# 04-POWER-P12V.net
KiCad netlist of a schematic drawn in Altium Designer
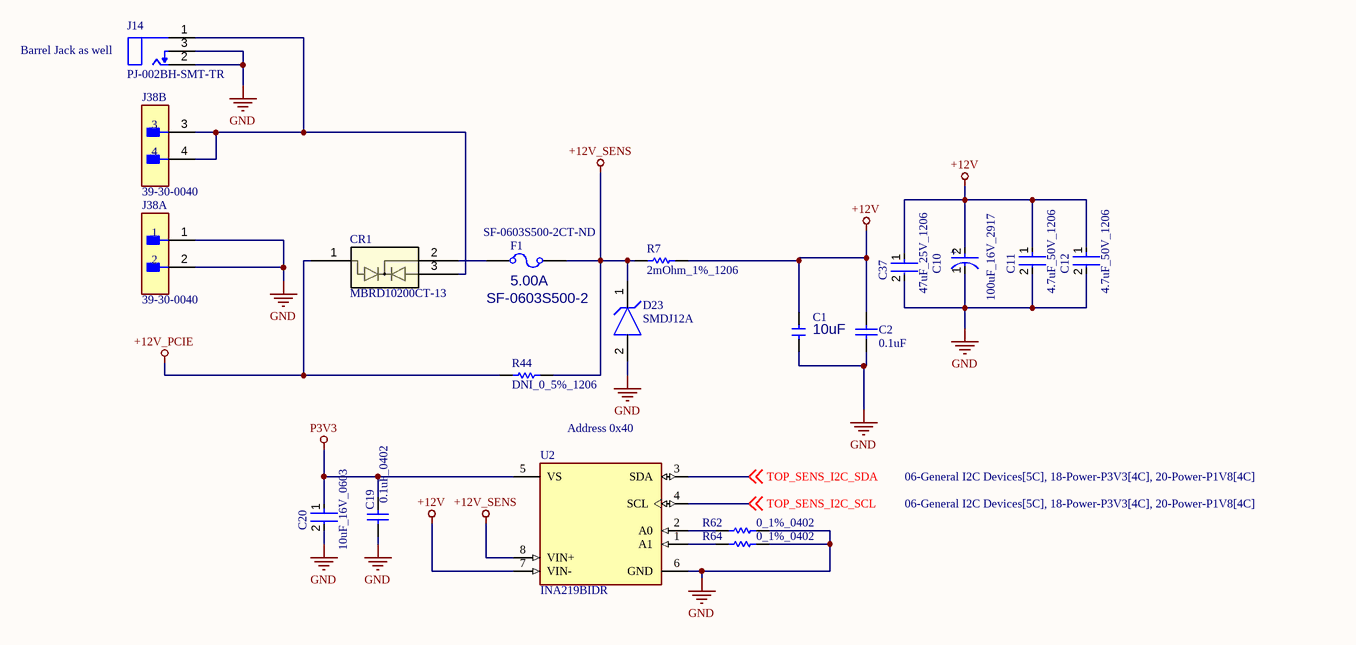
[diagram p0: 04-POWER-P12V.SchDoc]

(export (version "E")
  (design (tool "Eeschema 10.0.6"))
  (components
    (comp (ref "C1")
      (value "10uF")
      (footprint "CAPC2012X14N")
      (description "CAP, CER, 10.UF, 25V, 10%, X5R, 0805")
      (fields
        (field (name "MFG PART NUM") "TMK212BBJ106KG-T")
        (field (name "VALENTIUM PART NUM") "<VALENTIUM>")
      )
      (libsource (lib "Capacitors") (part "CAP_0805_10UF_25V"))
    )
    (comp (ref "C2")
      (value "0.1uF")
      (footprint "CAPC1608X87X45ML20T05")
      (description "C0603X104K5RACAUTO")
      (fields (field (name "MANUFACTURER") "Kemet"))
      (libsource (lib "Altium Content Vault") (part "CAP"))
    )
    (comp (ref "C10")
      (value "100uF_16V_2917")
      (footprint "FP-T495D107K016ATE125-MFG")
      (description "CAP TANT 100UF 10% 16V 2917")
      (fields (field (name "VOLTAGE") "16V") (field (name "TOLERANCE") "10%"))
      (libsource (lib "Altium Content Vault") (part "a00bbbee19879c290e62620ae7e47b1"))
    )
    (comp (ref "C11")
      (value "4.7uF_50V_1206")
      (footprint "FP-GRM31C-0_2-e0_3_0_8-IPC_C")
      (description "Chip Multilayer Ceramic Capacitors for General Purpose, 1206, 4.7uF, X7R, 15%, 10%, 50V")
      (fields (field (name "VOLTAGE") "50V") (field (name "TOLERANCE") "10%"))
      (libsource (lib "Altium Content Vault") (part "02cd4be3c70576c341d710602a673aa"))
    )
    (comp (ref "C12")
      (value "4.7uF_50V_1206")
      (footprint "FP-GRM31C-0_2-e0_3_0_8-IPC_C")
      (description "Chip Multilayer Ceramic Capacitors for General Purpose, 1206, 4.7uF, X7R, 15%, 10%, 50V")
      (fields (field (name "VOLTAGE") "50V") (field (name "TOLERANCE") "10%"))
      (libsource (lib "Altium Content Vault") (part "02cd4be3c70576c341d710602a673aa"))
    )
    (comp (ref "C19")
      (value "0.1uF_0402")
      (footprint "CAPC1005X56X25NL10T15")
      (fields
        (field (name "PART NUMBER") "LD02YD104KAB2A")
        (field (name "MANUFACTURER") "AVX Interconnect / Elco")
      )
      (libsource (lib "Altium Content Vault") (part "CAP"))
    )
    (comp (ref "C20")
      (value "10uF_16V_0603")
      (footprint "FP-0603-L_1_6_0_2-W_0_8_0-MFG")
      (description "Multilayer Ceramic Capacitor 10uF 16V X5R 20% SMD 0603 T/R")
      (fields (field (name "TOLERANCE") "20%"))
      (libsource (lib "Altium Content Vault") (part "b4654b650e69147ec39a6b967a45e02"))
    )
    (comp (ref "C37")
      (value "47uF_25V_1206")
      (footprint "FP-C3216-160-0_2-MFG")
      (description "Multilayer Ceramic Capacitors 47uF ±20% 25V X5R SMD 1206")
      (fields (field (name "VOLTAGE") "25V") (field (name "TOLERANCE") "20%"))
      (libsource (lib "Altium Content Vault") (part "11868f565c42a9108669ba33697ecf6"))
    )
    (comp (ref "CR1")
      (value "MBRD10200CT-13")
      (footprint "TO252(DPAK)_DIO")
      (description "No Description Available")
      (libsource (lib "MBRD10200CT-13") (part "MBRD10200CT-13"))
    )
    (comp (ref "D23")
      (value "SMDJ12A")
      (footprint "FP-DO-214AB_SMC_J-Bend-MFG")
      (description "TVS DIODE 12V 19.9V DO214AB")
      (libsource (lib "Altium Content Vault") (part "673ecd2ea4d7fb87b4005b0cb348b7d"))
    )
    (comp (ref "F1")
      (value "5.00A")
      (footprint "FUSM1608X60N")
      (description "FUSE SLOW 5.00A 32V M 0603")
      (fields
        (field (name "MFG PART NUM") "SF-0603S500-2")
        (field (name "VALENTIUM PART NUM") "<VALENTIUM>")
        (field (name "SUPPLIER PART NUMBER 1") "SF-0603S500-2CT-ND")
        (field (name "Comment") "FUSE_0603_5.00A")
      )
      (libsource (lib "Passives") (part "FUSE_0603_2.00A"))
    )
    (comp (ref "J14")
      (value "PJ-002BH-SMT-TR")
      (footprint "FP-PJ-002BH-SMT-TR-MFG")
      (description "CONN PWR JACK 2.5X5.5MM SOLDER")
      (fields
        (field (name "MANUFACTURER") "CUI Inc")
        (field (name "OCTOPART") "https://octopart.com/pj-002bh-smt-tr-cui-25947151")
      )
      (libsource (lib "Altium Content Vault") (part "020ff674638626da6de6501228ee46e"))
    )
    (comp (ref "J38")
      (value "39-30-0040")
      (footprint "FP-39-30-0040-MFG")
      (description "CONN HEADER R/A 4POS 4.2MM")
      (fields
        (field (name "OCTOPART") "https://octopart.com/39-30-0040-molex-277428")
        (field (name "MANUFACTURER") "Molex")
      )
      (libsource (lib "Altium Content Vault") (part "ac72c5313ea981db199dbd0e8237b04"))
    )
    (comp (ref "R7")
      (value "2mOhm_1%_1206")
      (footprint "RESC3216X89X64NL25T25")
      (fields (field (name "MANUFACTURER") "Vishay Dale") (field (name "PART NUMBER") "WSL12062L000FEA18"))
      (libsource (lib "Altium Content Vault") (part "RES"))
    )
    (comp (ref "R44")
      (value "DNI_0_5%_1206")
      (footprint "RESC3116X65X50ML20T20")
      (fields (field (name "PART NUMBER") "CRCW12060000Z0EAHP") (field (name "MANUFACTURER") "Vishay Dale"))
      (libsource (lib "Altium Content Vault") (part "RES"))
    )
    (comp (ref "R62")
      (value "0_1%_0402")
      (footprint "RESC1005X40X25LL05T05")
      (description "Chip Resistor, 0 Ohm, 0.1 W, -55 to 155 degC, 0402 (1005 Metric), RoHS, Tape and Reel")
      (fields (field (name "MANUFACTURER") "Panasonic") (field (name "TOLERANCE") "5%"))
      (libsource (lib "Altium Content Vault") (part "RES-2"))
    )
    (comp (ref "R64")
      (value "0_1%_0402")
      (footprint "RESC1005X40X25LL05T05")
      (description "Chip Resistor, 0 Ohm, 0.1 W, -55 to 155 degC, 0402 (1005 Metric), RoHS, Tape and Reel")
      (fields (field (name "MANUFACTURER") "Panasonic") (field (name "TOLERANCE") "5%"))
      (libsource (lib "Altium Content Vault") (part "RES-2"))
    )
    (comp (ref "U2")
      (value "INA219BIDR")
      (footprint "FP-D0008A-MFG")
      (description "IC MONITOR PWR/CURR BIDIR 8-SOIC")
      (libsource (lib "Altium Content Vault") (part "41cc1aee4cbc9fa2660a15773fa0e79"))
    )
  )
  (nets
    (net (code "1") (name "+12V") (class "Default")
      (node (ref "C1") (pin "1") (pinfunction "1_1") (pintype "passive"))
      (node (ref "C10") (pin "2") (pinfunction "A_2") (pintype "passive"))
      (node (ref "C11") (pin "1") (pinfunction "1_1") (pintype "passive"))
      (node (ref "C12") (pin "1") (pinfunction "1_1") (pintype "passive"))
      (node (ref "C2") (pin "2") (pinfunction "2_2") (pintype "passive"))
      (node (ref "C37") (pin "1") (pinfunction "1_1") (pintype "passive"))
      (node (ref "R7") (pin "2") (pinfunction "2_2") (pintype "passive"))
      (node (ref "U2") (pin "7") (pinfunction "VIN-_7") (pintype "input"))
    )
    (net (code "2") (name "+12V_PCIE") (class "Default")
      (node (ref "CR1") (pin "1") (pinfunction "1_1") (pintype "passive"))
      (node (ref "R44") (pin "1") (pinfunction "1_1") (pintype "passive"))
    )
    (net (code "3") (name "+12V_SENS") (class "Default")
      (node (ref "D23") (pin "1") (pinfunction "C_1") (pintype "passive"))
      (node (ref "F1") (pin "2") (pinfunction "2_2") (pintype "passive"))
      (node (ref "R44") (pin "2") (pinfunction "2_2") (pintype "passive"))
      (node (ref "R7") (pin "1") (pinfunction "1_1") (pintype "passive"))
      (node (ref "U2") (pin "8") (pinfunction "VIN+_8") (pintype "input"))
    )
    (net (code "4") (name "GND") (class "Default")
      (node (ref "C1") (pin "2") (pinfunction "2_2") (pintype "passive"))
      (node (ref "C10") (pin "1") (pinfunction "C_1") (pintype "passive"))
      (node (ref "C11") (pin "2") (pinfunction "2_2") (pintype "passive"))
      (node (ref "C12") (pin "2") (pinfunction "2_2") (pintype "passive"))
      (node (ref "C19") (pin "1") (pinfunction "1_1") (pintype "passive"))
      (node (ref "C2") (pin "1") (pinfunction "1_1") (pintype "passive"))
      (node (ref "C20") (pin "2") (pinfunction "2_2") (pintype "passive"))
      (node (ref "C37") (pin "2") (pinfunction "2_2") (pintype "passive"))
      (node (ref "D23") (pin "2") (pinfunction "A_2") (pintype "passive"))
      (node (ref "J14") (pin "2") (pinfunction "2_2") (pintype "passive"))
      (node (ref "J14") (pin "3") (pinfunction "3_3") (pintype "passive"))
      (node (ref "J38") (pin "1") (pinfunction "1_1") (pintype "passive"))
      (node (ref "J38") (pin "2") (pinfunction "2_2") (pintype "passive"))
      (node (ref "R62") (pin "2") (pinfunction "2_2") (pintype "passive"))
      (node (ref "R64") (pin "2") (pinfunction "2_2") (pintype "passive"))
      (node (ref "U2") (pin "6") (pinfunction "GND_6") (pintype "power_in"))
    )
    (net (code "5") (name "Net-(CR1-Pad2)") (class "Default")
      (node (ref "CR1") (pin "2") (pinfunction "2_2") (pintype "passive"))
      (node (ref "F1") (pin "1") (pinfunction "1_1") (pintype "passive"))
    )
    (net (code "6") (name "Net-(CR1-Pad3)") (class "Default")
      (node (ref "CR1") (pin "3") (pinfunction "3_3") (pintype "passive"))
      (node (ref "J14") (pin "1") (pinfunction "1_1") (pintype "passive"))
      (node (ref "J38") (pin "3") (pinfunction "3_3") (pintype "passive"))
      (node (ref "J38") (pin "4") (pinfunction "4_4") (pintype "passive"))
    )
    (net (code "7") (name "Net-(U2-A0)") (class "Default")
      (node (ref "R62") (pin "1") (pinfunction "1_1") (pintype "passive"))
      (node (ref "U2") (pin "2") (pinfunction "A0_2") (pintype "input"))
    )
    (net (code "8") (name "Net-(U2-A1)") (class "Default")
      (node (ref "R64") (pin "1") (pinfunction "1_1") (pintype "passive"))
      (node (ref "U2") (pin "1") (pinfunction "A1_1") (pintype "input"))
    )
    (net (code "9") (name "P3V3") (class "Default")
      (node (ref "C19") (pin "2") (pinfunction "2_2") (pintype "passive"))
      (node (ref "C20") (pin "1") (pinfunction "1_1") (pintype "passive"))
      (node (ref "U2") (pin "5") (pinfunction "VS_5") (pintype "power_in"))
    )
    (net (code "10") (name "TOP_SENS_I2C_SCL") (class "Default")
      (node (ref "U2") (pin "4") (pinfunction "SCL_4") (pintype "bidirectional"))
    )
    (net (code "11") (name "TOP_SENS_I2C_SDA") (class "Default")
      (node (ref "U2") (pin "3") (pinfunction "SDA_3") (pintype "bidirectional"))
    )
  )
)
